# SCH_PAYLOAD_2022-04-15.net
KiCad netlist of a schematic drawn in EasyEDA
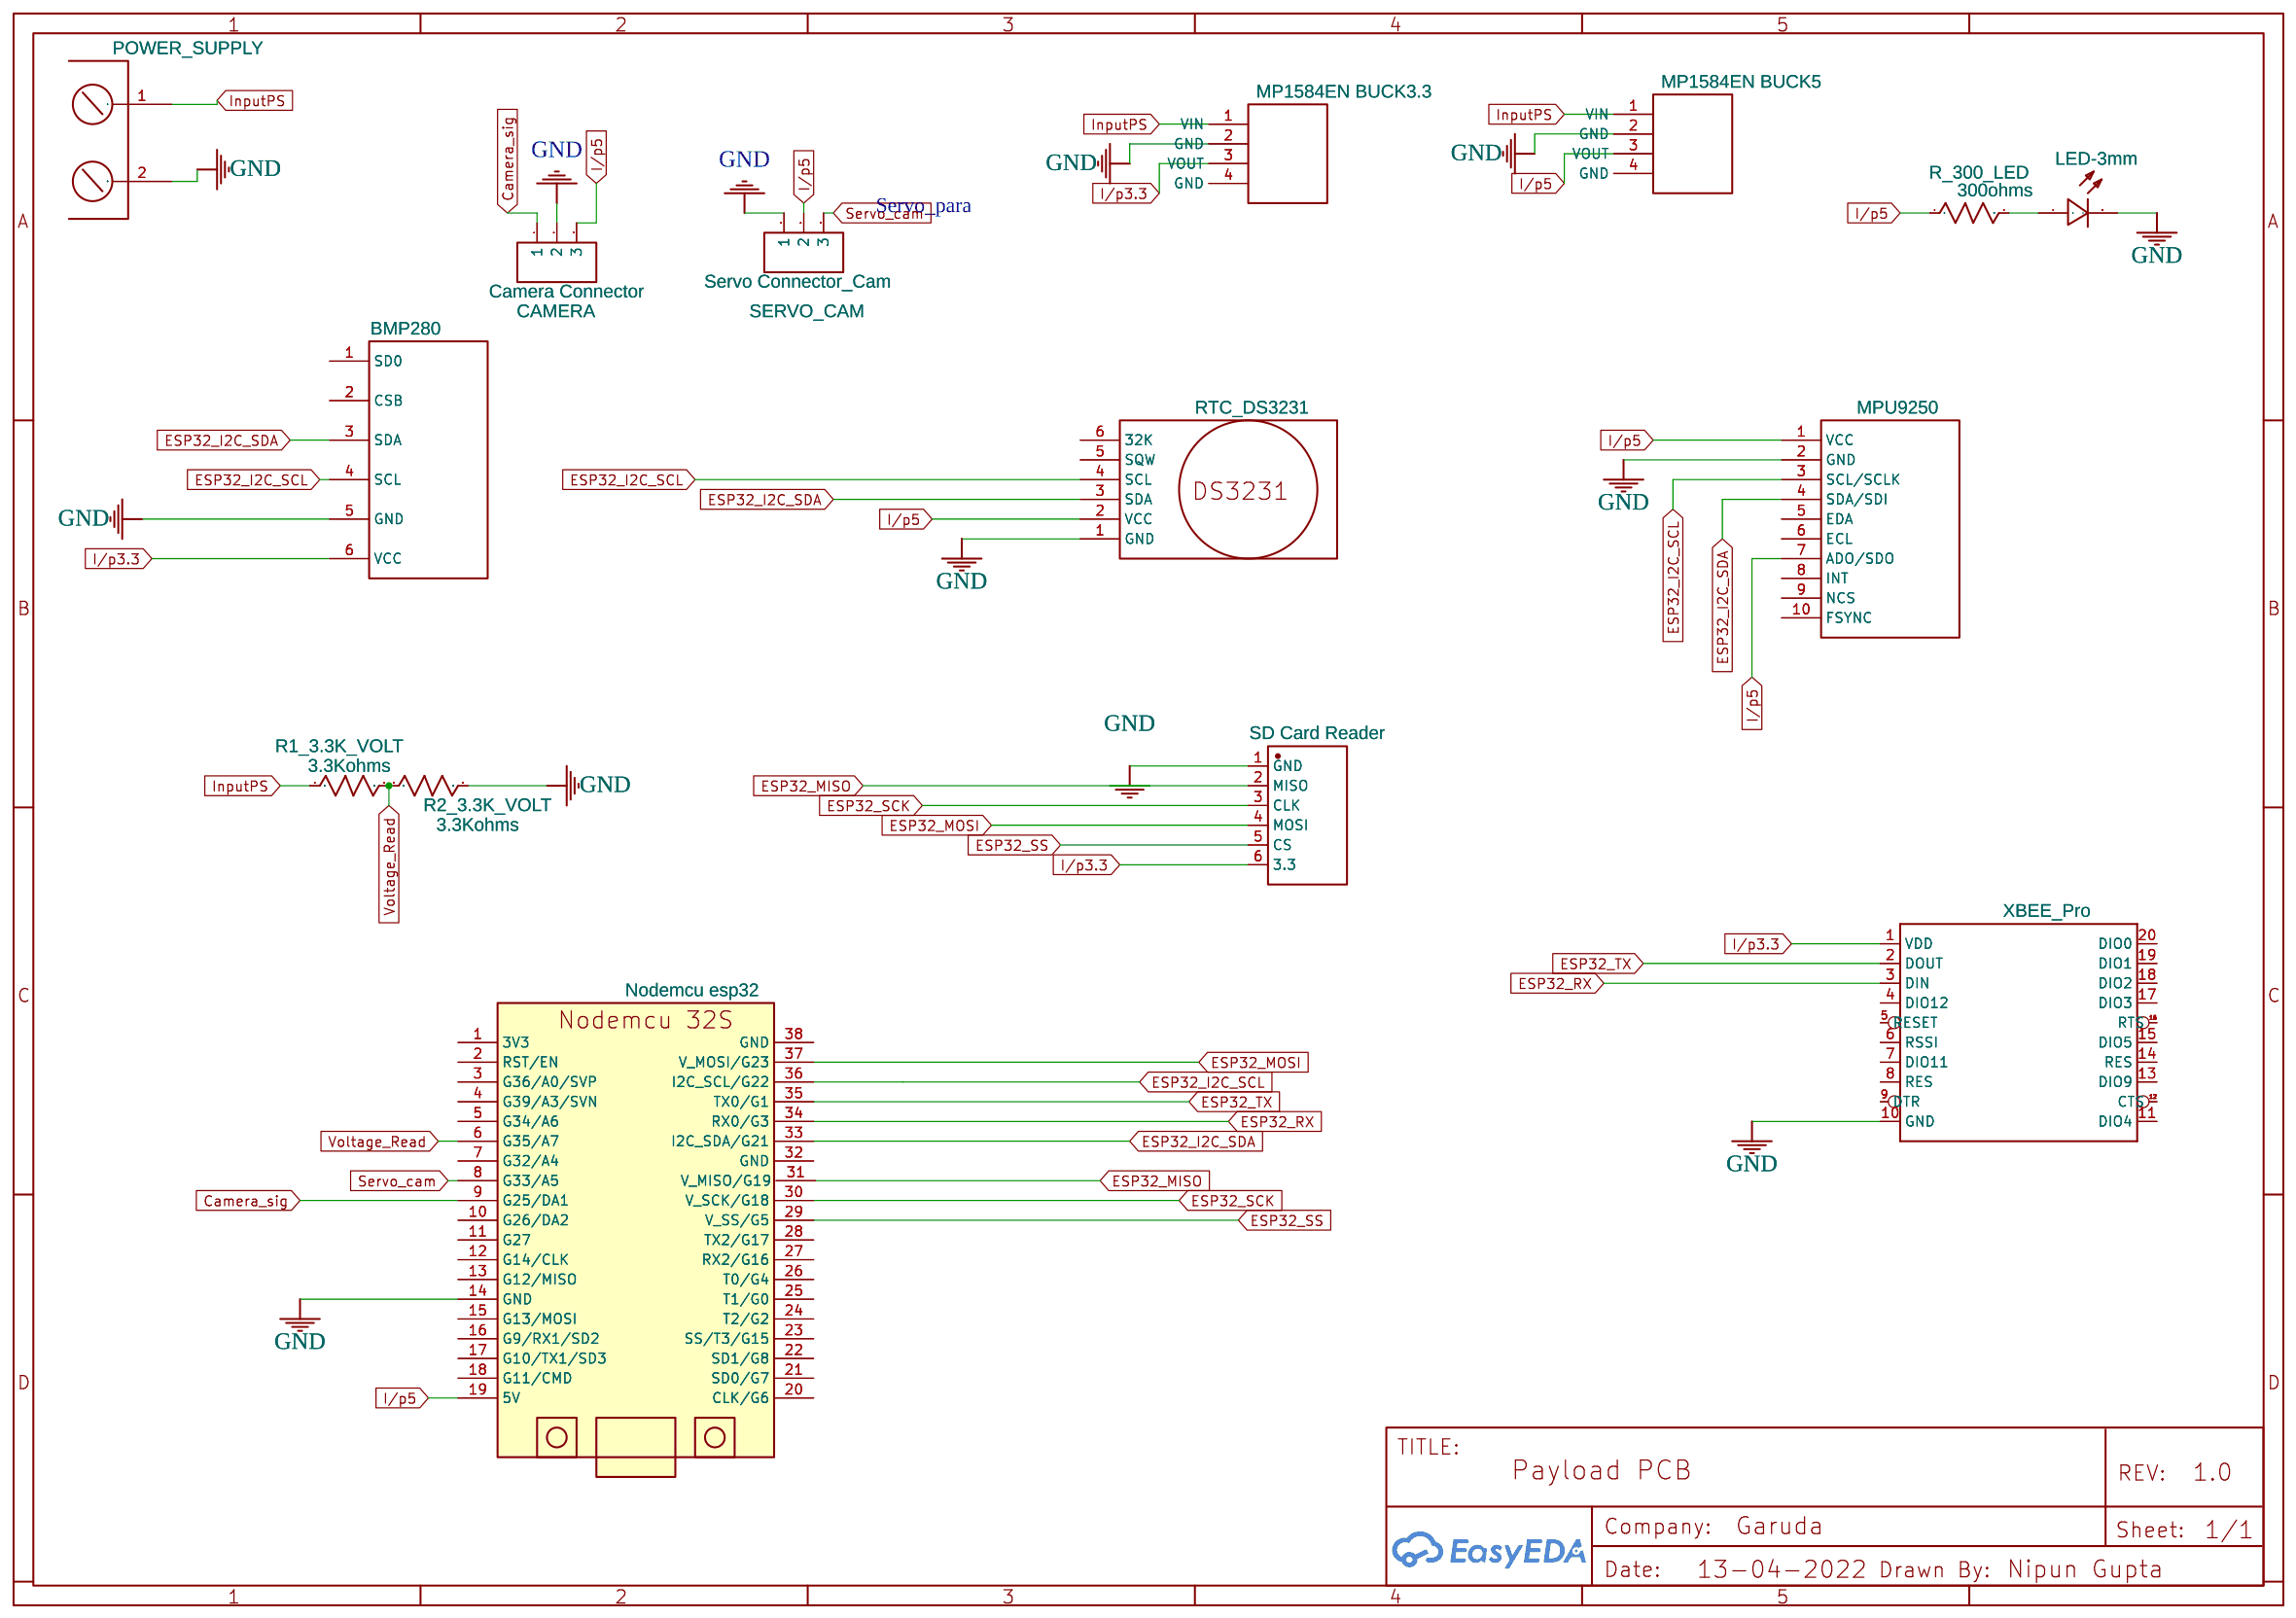
[diagram p0: schematic sheet]

(export (version "E")
  (design (tool "Eeschema 10.0.6"))
  (components
    (comp (ref "CAMERA")
      (value "Camera Connector")
      (fields
        (field (name "BOM_Manufacturer Part") "Header-Female-2.54_1x3")
        (field (name "BOM_Supplier Part") "C146243")
      )
      (libsource (lib "") (part "Header-Female-2.54_1x3"))
    )
    (comp (ref "J1") (value "POWER_SUPPLY") (libsource (lib "") (part "2pin_5A_TerminalBlock")))
    (comp (ref "JP2") (value "XBEE_Pro") (libsource (lib "") (part "XBEE_Pro")))
    (comp (ref "LED1")
      (value "LED-3mm")
      (fields
        (field (name "BOM_Manufacturer Part") "204-10SURD/S530-A3")
        (field (name "BOM_Supplier Part") "C99772")
      )
      (libsource (lib "") (part "Unknown_1045_-710"))
    )
    (comp (ref "PRESS1")
      (value "BMP280")
      (fields (field (name "BOM_Manufacturer Part") "?"))
      (libsource (lib "") (part "BMP280 Sparkfun"))
    )
    (comp (ref "R1_3.3K_VOLT")
      (value "3.3Kohms")
      (fields (field (name "BOM_Manufacturer Part") "?"))
      (libsource (lib "") (part "Res_AXIAL-0.3(1/8W)_US_2"))
    )
    (comp (ref "R2_3.3K_VOLT")
      (value "3.3Kohms")
      (fields (field (name "BOM_Manufacturer Part") "?"))
      (libsource (lib "") (part "Res_AXIAL-0.3(1/8W)_US_1"))
    )
    (comp (ref "R_300_LED")
      (value "300ohms")
      (fields (field (name "BOM_Manufacturer Part") "?"))
      (libsource (lib "") (part "Res_AXIAL-0.3(1/8W)_US"))
    )
    (comp (ref "S1")
      (value "MPU9250")
      (fields (field (name "BOM_Supplier Part") "GY-9250"))
      (libsource (lib "") (part "MPU9250-MDL NO HOLES"))
    )
    (comp (ref "SD-READER3")
      (value "SD Card Reader")
      (fields (field (name "BOM_Manufacturer Part") "SD card reader 17.9x17.9"))
      (libsource (lib "") (part "Micro SD Card Reader"))
    )
    (comp (ref "SERVO_CAM")
      (value "Servo Connector_Cam")
      (fields
        (field (name "BOM_Manufacturer Part") "Header-Female-2.54_1x3")
        (field (name "BOM_Supplier Part") "C146243")
      )
      (libsource (lib "") (part "Header-Female-2.54_1x3_1"))
    )
    (comp (ref "U2") (value "MP1584EN BUCK5") (libsource (lib "") (part "MP1584EN COPY")))
    (comp (ref "U3") (value "MP1584EN BUCK3.3") (libsource (lib "") (part "MP1584EN COPY")))
    (comp (ref "U9") (value "RTC_DS3231") (libsource (lib "") (part "UhrModul_DS3231")))
    (comp (ref "U11") (value "Nodemcu esp32") (libsource (lib "") (part "Nodemcu esp32")))
  )
  (nets
    (net (code "1") (name "Camera_sig") (class "Default")
      (node (ref "CAMERA") (pin "1") (pinfunction "1_1") (pintype "input"))
      (node (ref "U11") (pin "9") (pinfunction "G25/DA1_9") (pintype "bidirectional"))
    )
    (net (code "2") (name "ESP32_I2C_SCL") (class "Default")
      (node (ref "PRESS1") (pin "4") (pinfunction "SCL_4") (pintype "unspecified"))
      (node (ref "S1") (pin "3") (pinfunction "SCL/SCLK_3") (pintype "unspecified"))
      (node (ref "U11") (pin "36") (pinfunction "I2C_SCL/G22_36") (pintype "bidirectional"))
      (node (ref "U9") (pin "4") (pinfunction "SCL_4") (pintype "unspecified"))
    )
    (net (code "3") (name "ESP32_I2C_SDA") (class "Default")
      (node (ref "PRESS1") (pin "3") (pinfunction "SDA_3") (pintype "unspecified"))
      (node (ref "S1") (pin "4") (pinfunction "SDA/SDI_4") (pintype "unspecified"))
      (node (ref "U11") (pin "33") (pinfunction "I2C_SDA/G21_33") (pintype "bidirectional"))
      (node (ref "U9") (pin "3") (pinfunction "SDA_3") (pintype "unspecified"))
    )
    (net (code "4") (name "ESP32_MISO") (class "Default")
      (node (ref "SD-READER3") (pin "2") (pinfunction "MISO_2") (pintype "unspecified"))
      (node (ref "U11") (pin "31") (pinfunction "V_MISO/G19_31") (pintype "bidirectional"))
    )
    (net (code "5") (name "ESP32_MOSI") (class "Default")
      (node (ref "SD-READER3") (pin "4") (pinfunction "MOSI_4") (pintype "unspecified"))
      (node (ref "U11") (pin "37") (pinfunction "V_MOSI/G23_37") (pintype "bidirectional"))
    )
    (net (code "6") (name "ESP32_RX") (class "Default")
      (node (ref "JP2") (pin "3") (pinfunction "DIN_3") (pintype "input"))
      (node (ref "U11") (pin "34") (pinfunction "RX0/G3_34") (pintype "bidirectional"))
    )
    (net (code "7") (name "ESP32_SCK") (class "Default")
      (node (ref "SD-READER3") (pin "3") (pinfunction "CLK_3") (pintype "unspecified"))
      (node (ref "U11") (pin "30") (pinfunction "V_SCK/G18_30") (pintype "bidirectional"))
    )
    (net (code "8") (name "ESP32_SS") (class "Default")
      (node (ref "SD-READER3") (pin "5") (pinfunction "CS_5") (pintype "unspecified"))
      (node (ref "U11") (pin "29") (pinfunction "V_SS/G5_29") (pintype "bidirectional"))
    )
    (net (code "9") (name "ESP32_TX") (class "Default")
      (node (ref "JP2") (pin "2") (pinfunction "DOUT_2") (pintype "output"))
      (node (ref "U11") (pin "35") (pinfunction "TX0/G1_35") (pintype "bidirectional"))
    )
    (net (code "10") (name "GND") (class "Default")
      (node (ref "CAMERA") (pin "2") (pinfunction "2_2") (pintype "input"))
      (node (ref "J1") (pin "2") (pinfunction "2_2") (pintype "unspecified"))
      (node (ref "JP2") (pin "10") (pinfunction "GND_10") (pintype "passive"))
      (node (ref "LED1") (pin "2") (pinfunction "-_2") (pintype "unspecified"))
      (node (ref "PRESS1") (pin "5") (pinfunction "GND_5") (pintype "unspecified"))
      (node (ref "R2_3.3K_VOLT") (pin "2") (pinfunction "2_2") (pintype "unspecified"))
      (node (ref "S1") (pin "2") (pinfunction "GND_2") (pintype "unspecified"))
      (node (ref "SD-READER3") (pin "1") (pinfunction "GND_1") (pintype "unspecified"))
      (node (ref "SERVO_CAM") (pin "1") (pinfunction "1_1") (pintype "input"))
      (node (ref "U11") (pin "14") (pinfunction "GND_14") (pintype "passive"))
      (node (ref "U2") (pin "2") (pinfunction "GND_2") (pintype "unspecified"))
      (node (ref "U3") (pin "2") (pinfunction "GND_2") (pintype "unspecified"))
      (node (ref "U9") (pin "1") (pinfunction "GND_1") (pintype "unspecified"))
    )
    (net (code "11") (name "InputPS") (class "Default")
      (node (ref "J1") (pin "1") (pinfunction "1_1") (pintype "unspecified"))
      (node (ref "R1_3.3K_VOLT") (pin "1") (pinfunction "1_1") (pintype "unspecified"))
      (node (ref "U2") (pin "1") (pinfunction "VIN_1") (pintype "unspecified"))
      (node (ref "U3") (pin "1") (pinfunction "VIN_1") (pintype "unspecified"))
    )
    (net (code "12") (name "I{slash}p3.3") (class "Default")
      (node (ref "JP2") (pin "1") (pinfunction "VDD_1") (pintype "passive"))
      (node (ref "PRESS1") (pin "6") (pinfunction "VCC_6") (pintype "unspecified"))
      (node (ref "SD-READER3") (pin "6") (pinfunction "3.3_6") (pintype "unspecified"))
      (node (ref "U3") (pin "3") (pinfunction "VOUT_3") (pintype "unspecified"))
    )
    (net (code "13") (name "I{slash}p5") (class "Default")
      (node (ref "CAMERA") (pin "3") (pinfunction "3_3") (pintype "input"))
      (node (ref "R_300_LED") (pin "1") (pinfunction "1_1") (pintype "unspecified"))
      (node (ref "S1") (pin "1") (pinfunction "VCC_1") (pintype "unspecified"))
      (node (ref "S1") (pin "7") (pinfunction "ADO/SDO_7") (pintype "unspecified"))
      (node (ref "SERVO_CAM") (pin "2") (pinfunction "2_2") (pintype "input"))
      (node (ref "U11") (pin "19") (pinfunction "5V_19") (pintype "passive"))
      (node (ref "U2") (pin "3") (pinfunction "VOUT_3") (pintype "unspecified"))
      (node (ref "U9") (pin "2") (pinfunction "VCC_2") (pintype "unspecified"))
    )
    (net (code "14") (name "Net-(LED1-+)") (class "Default")
      (node (ref "LED1") (pin "1") (pinfunction "+_1") (pintype "unspecified"))
      (node (ref "R_300_LED") (pin "2") (pinfunction "2_2") (pintype "unspecified"))
    )
    (net (code "15") (name "Servo_cam") (class "Default")
      (node (ref "SERVO_CAM") (pin "3") (pinfunction "3_3") (pintype "input"))
      (node (ref "U11") (pin "8") (pinfunction "G33/A5_8") (pintype "bidirectional"))
    )
    (net (code "16") (name "Voltage_Read") (class "Default")
      (node (ref "R1_3.3K_VOLT") (pin "2") (pinfunction "2_2") (pintype "unspecified"))
      (node (ref "R2_3.3K_VOLT") (pin "1") (pinfunction "1_1") (pintype "unspecified"))
      (node (ref "U11") (pin "6") (pinfunction "G35/A7_6") (pintype "bidirectional"))
    )
    (net (code "17") (name "unconnected-(JP2-CTS-Pad12)") (class "Default")
      (node (ref "JP2") (pin "12") (pinfunction "CTS_12") (pintype "output"))
    )
    (net (code "18") (name "unconnected-(JP2-DIO0-Pad20)") (class "Default")
      (node (ref "JP2") (pin "20") (pinfunction "DIO0_20") (pintype "unspecified"))
    )
    (net (code "19") (name "unconnected-(JP2-DIO1-Pad19)") (class "Default")
      (node (ref "JP2") (pin "19") (pinfunction "DIO1_19") (pintype "unspecified"))
    )
    (net (code "20") (name "unconnected-(JP2-DIO2-Pad18)") (class "Default")
      (node (ref "JP2") (pin "18") (pinfunction "DIO2_18") (pintype "unspecified"))
    )
    (net (code "21") (name "unconnected-(JP2-DIO3-Pad17)") (class "Default")
      (node (ref "JP2") (pin "17") (pinfunction "DIO3_17") (pintype "unspecified"))
    )
    (net (code "22") (name "unconnected-(JP2-DIO4-Pad11)") (class "Default")
      (node (ref "JP2") (pin "11") (pinfunction "DIO4_11") (pintype "unspecified"))
    )
    (net (code "23") (name "unconnected-(JP2-DIO5-Pad15)") (class "Default")
      (node (ref "JP2") (pin "15") (pinfunction "DIO5_15") (pintype "unspecified"))
    )
    (net (code "24") (name "unconnected-(JP2-DIO9-Pad13)") (class "Default")
      (node (ref "JP2") (pin "13") (pinfunction "DIO9_13") (pintype "unspecified"))
    )
    (net (code "25") (name "unconnected-(JP2-DIO11-Pad7)") (class "Default")
      (node (ref "JP2") (pin "7") (pinfunction "DIO11_7") (pintype "unspecified"))
    )
    (net (code "26") (name "unconnected-(JP2-DIO12-Pad4)") (class "Default")
      (node (ref "JP2") (pin "4") (pinfunction "DIO12_4") (pintype "unspecified"))
    )
    (net (code "27") (name "unconnected-(JP2-DTR-Pad9)") (class "Default")
      (node (ref "JP2") (pin "9") (pinfunction "DTR_9") (pintype "unspecified"))
    )
    (net (code "28") (name "unconnected-(JP2-RES-Pad8)") (class "Default")
      (node (ref "JP2") (pin "8") (pinfunction "RES_8") (pintype "unspecified"))
    )
    (net (code "29") (name "unconnected-(JP2-RES-Pad14)") (class "Default")
      (node (ref "JP2") (pin "14") (pinfunction "RES_14") (pintype "unspecified"))
    )
    (net (code "30") (name "unconnected-(JP2-RESET-Pad5)") (class "Default")
      (node (ref "JP2") (pin "5") (pinfunction "RESET_5") (pintype "input"))
    )
    (net (code "31") (name "unconnected-(JP2-RSSI-Pad6)") (class "Default")
      (node (ref "JP2") (pin "6") (pinfunction "RSSI_6") (pintype "unspecified"))
    )
    (net (code "32") (name "unconnected-(JP2-RTS-Pad16)") (class "Default")
      (node (ref "JP2") (pin "16") (pinfunction "RTS_16") (pintype "input"))
    )
    (net (code "33") (name "unconnected-(PRESS1-CSB-Pad2)") (class "Default")
      (node (ref "PRESS1") (pin "2") (pinfunction "CSB_2") (pintype "unspecified"))
    )
    (net (code "34") (name "unconnected-(PRESS1-SD0-Pad1)") (class "Default")
      (node (ref "PRESS1") (pin "1") (pinfunction "SD0_1") (pintype "unspecified"))
    )
    (net (code "35") (name "unconnected-(S1-ECL-Pad6)") (class "Default")
      (node (ref "S1") (pin "6") (pinfunction "ECL_6") (pintype "unspecified"))
    )
    (net (code "36") (name "unconnected-(S1-EDA-Pad5)") (class "Default")
      (node (ref "S1") (pin "5") (pinfunction "EDA_5") (pintype "unspecified"))
    )
    (net (code "37") (name "unconnected-(S1-FSYNC-Pad10)") (class "Default")
      (node (ref "S1") (pin "10") (pinfunction "FSYNC_10") (pintype "unspecified"))
    )
    (net (code "38") (name "unconnected-(S1-INT-Pad8)") (class "Default")
      (node (ref "S1") (pin "8") (pinfunction "INT_8") (pintype "unspecified"))
    )
    (net (code "39") (name "unconnected-(S1-NCS-Pad9)") (class "Default")
      (node (ref "S1") (pin "9") (pinfunction "NCS_9") (pintype "unspecified"))
    )
    (net (code "40") (name "unconnected-(U2-GND-Pad4)") (class "Default")
      (node (ref "U2") (pin "4") (pinfunction "GND_4") (pintype "unspecified"))
    )
    (net (code "41") (name "unconnected-(U3-GND-Pad4)") (class "Default")
      (node (ref "U3") (pin "4") (pinfunction "GND_4") (pintype "unspecified"))
    )
    (net (code "42") (name "unconnected-(U9-32K-Pad6)") (class "Default")
      (node (ref "U9") (pin "6") (pinfunction "32K_6") (pintype "unspecified"))
    )
    (net (code "43") (name "unconnected-(U9-SQW-Pad5)") (class "Default")
      (node (ref "U9") (pin "5") (pinfunction "SQW_5") (pintype "unspecified"))
    )
    (net (code "44") (name "unconnected-(U11-3V3-Pad1)") (class "Default")
      (node (ref "U11") (pin "1") (pinfunction "3V3_1") (pintype "passive"))
    )
    (net (code "45") (name "unconnected-(U11-CLK{slash}G6-Pad20)") (class "Default")
      (node (ref "U11") (pin "20") (pinfunction "CLK/G6_20") (pintype "bidirectional"))
    )
    (net (code "46") (name "unconnected-(U11-G9{slash}RX1{slash}SD2-Pad16)") (class "Default")
      (node (ref "U11") (pin "16") (pinfunction "G9/RX1/SD2_16") (pintype "bidirectional"))
    )
    (net (code "47") (name "unconnected-(U11-G10{slash}TX1{slash}SD3-Pad17)") (class "Default")
      (node (ref "U11") (pin "17") (pinfunction "G10/TX1/SD3_17") (pintype "bidirectional"))
    )
    (net (code "48") (name "unconnected-(U11-G11{slash}CMD-Pad18)") (class "Default")
      (node (ref "U11") (pin "18") (pinfunction "G11/CMD_18") (pintype "bidirectional"))
    )
    (net (code "49") (name "unconnected-(U11-G12{slash}MISO-Pad13)") (class "Default")
      (node (ref "U11") (pin "13") (pinfunction "G12/MISO_13") (pintype "bidirectional"))
    )
    (net (code "50") (name "unconnected-(U11-G13{slash}MOSI-Pad15)") (class "Default")
      (node (ref "U11") (pin "15") (pinfunction "G13/MOSI_15") (pintype "bidirectional"))
    )
    (net (code "51") (name "unconnected-(U11-G14{slash}CLK-Pad12)") (class "Default")
      (node (ref "U11") (pin "12") (pinfunction "G14/CLK_12") (pintype "bidirectional"))
    )
    (net (code "52") (name "unconnected-(U11-G26{slash}DA2-Pad10)") (class "Default")
      (node (ref "U11") (pin "10") (pinfunction "G26/DA2_10") (pintype "bidirectional"))
    )
    (net (code "53") (name "unconnected-(U11-G27-Pad11)") (class "Default")
      (node (ref "U11") (pin "11") (pinfunction "G27_11") (pintype "bidirectional"))
    )
    (net (code "54") (name "unconnected-(U11-G32{slash}A4-Pad7)") (class "Default")
      (node (ref "U11") (pin "7") (pinfunction "G32/A4_7") (pintype "bidirectional"))
    )
    (net (code "55") (name "unconnected-(U11-G34{slash}A6-Pad5)") (class "Default")
      (node (ref "U11") (pin "5") (pinfunction "G34/A6_5") (pintype "bidirectional"))
    )
    (net (code "56") (name "unconnected-(U11-G36{slash}A0{slash}SVP-Pad3)") (class "Default")
      (node (ref "U11") (pin "3") (pinfunction "G36/A0/SVP_3") (pintype "bidirectional"))
    )
    (net (code "57") (name "unconnected-(U11-G39{slash}A3{slash}SVN-Pad4)") (class "Default")
      (node (ref "U11") (pin "4") (pinfunction "G39/A3/SVN_4") (pintype "bidirectional"))
    )
    (net (code "58") (name "unconnected-(U11-GND-Pad32)") (class "Default")
      (node (ref "U11") (pin "32") (pinfunction "GND_32") (pintype "passive"))
    )
    (net (code "59") (name "unconnected-(U11-GND-Pad38)") (class "Default")
      (node (ref "U11") (pin "38") (pinfunction "GND_38") (pintype "passive"))
    )
    (net (code "60") (name "unconnected-(U11-RST{slash}EN-Pad2)") (class "Default")
      (node (ref "U11") (pin "2") (pinfunction "RST/EN_2") (pintype "bidirectional"))
    )
    (net (code "61") (name "unconnected-(U11-RX2{slash}G16-Pad27)") (class "Default")
      (node (ref "U11") (pin "27") (pinfunction "RX2/G16_27") (pintype "bidirectional"))
    )
    (net (code "62") (name "unconnected-(U11-SD0{slash}G7-Pad21)") (class "Default")
      (node (ref "U11") (pin "21") (pinfunction "SD0/G7_21") (pintype "bidirectional"))
    )
    (net (code "63") (name "unconnected-(U11-SD1{slash}G8-Pad22)") (class "Default")
      (node (ref "U11") (pin "22") (pinfunction "SD1/G8_22") (pintype "bidirectional"))
    )
    (net (code "64") (name "unconnected-(U11-SS{slash}T3{slash}G15-Pad23)") (class "Default")
      (node (ref "U11") (pin "23") (pinfunction "SS/T3/G15_23") (pintype "bidirectional"))
    )
    (net (code "65") (name "unconnected-(U11-T0{slash}G4-Pad26)") (class "Default")
      (node (ref "U11") (pin "26") (pinfunction "T0/G4_26") (pintype "bidirectional"))
    )
    (net (code "66") (name "unconnected-(U11-T1{slash}G0-Pad25)") (class "Default")
      (node (ref "U11") (pin "25") (pinfunction "T1/G0_25") (pintype "bidirectional"))
    )
    (net (code "67") (name "unconnected-(U11-T2{slash}G2-Pad24)") (class "Default")
      (node (ref "U11") (pin "24") (pinfunction "T2/G2_24") (pintype "bidirectional"))
    )
    (net (code "68") (name "unconnected-(U11-TX2{slash}G17-Pad28)") (class "Default")
      (node (ref "U11") (pin "28") (pinfunction "TX2/G17_28") (pintype "bidirectional"))
    )
  )
)
